# Window_Garden.net
KiCad netlist of a schematic drawn in Altium Designer
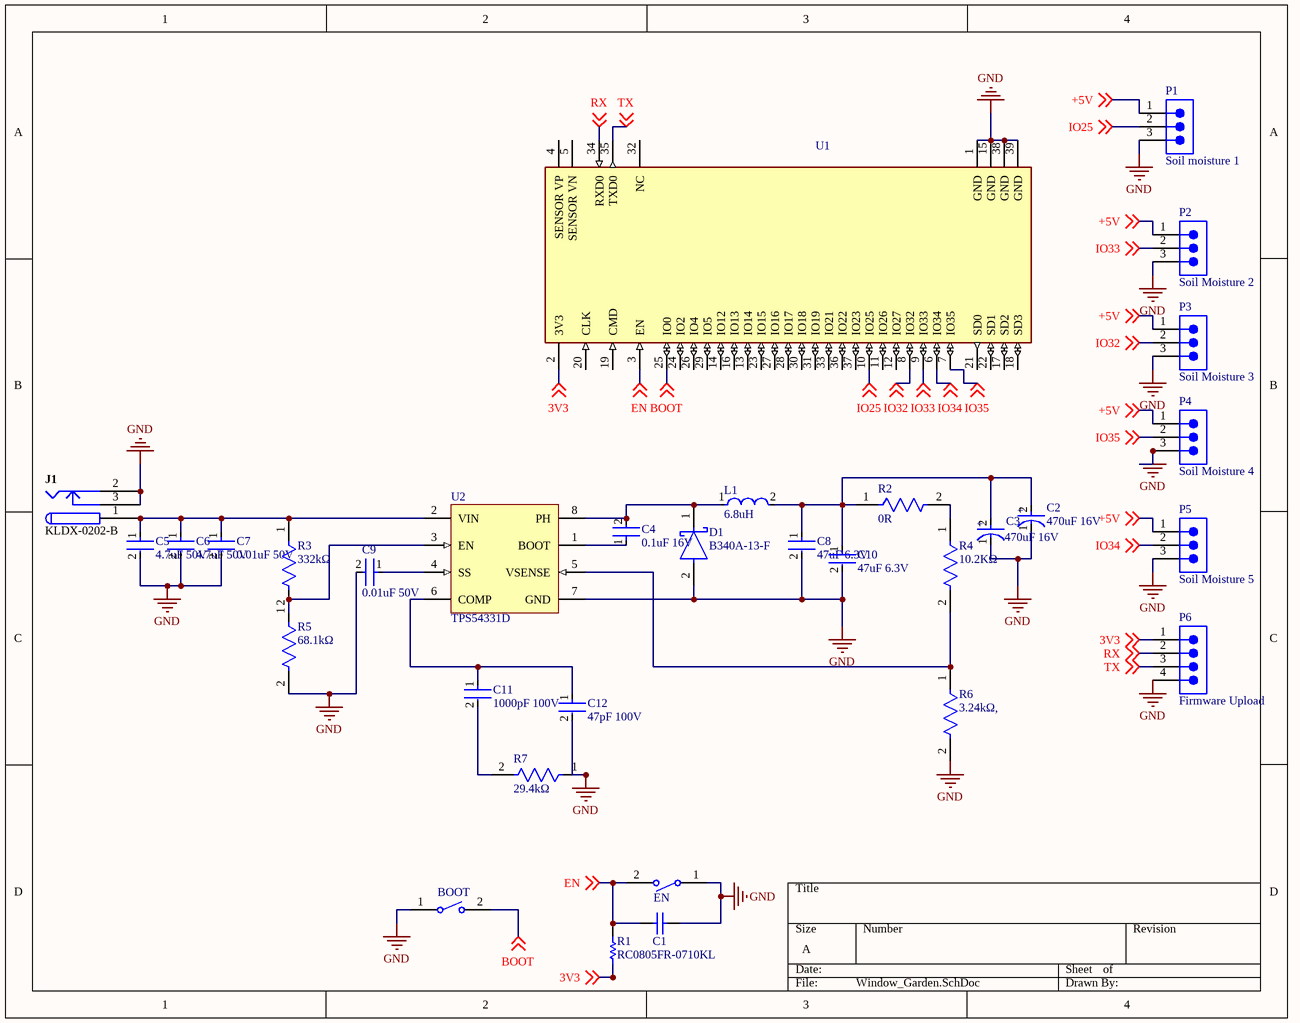
[diagram p0: Window_Garden.SchDoc]

(export (version "E")
  (design (tool "Eeschema 10.0.6"))
  (components
    (comp (ref "BOOT")
      (value "FSMSMTR")
      (footprint "TECO-FSMSMTR_V")
      (description "FSMSM Push Button Switch, 50 mA, -35 to 85 degC, 2-Pin SMD, RoHS, Tape and Reel")
      (fields (field (name "MANUFACTURER") "TE Connectivity"))
      (libsource (lib "Altium Content Vault") (part "SW-SPST-2_C"))
    )
    (comp (ref "C1")
      (value "GRM188R71H104KA93D")
      (footprint "CAPC1608X90X35ML10T15")
      (description "Chip Capacitor, 0.1 uF, +/- 10%, 50 V, -55 to 125 degC, 0603 (1608 Metric), RoHS, Tape and Reel")
      (fields (field (name "TOLERANCE") "10%") (field (name "VOLTAGE") "50V"))
      (libsource (lib "Altium Content Vault") (part "CAP-NP-2"))
    )
    (comp (ref "C2")
      (value "470uF 16V")
      (footprint "FP-RAD-TH-D_8_0_5-L_11_5-MFG")
      (description "Aluminum Electrolytic Capacitors (Radial Lead Type) 470uF ±20% 16V")
      (fields (field (name "TOLERANCE") "20%"))
      (libsource (lib "Altium Content Vault") (part "a00bbbee19879c290e62620ae7e47b1"))
    )
    (comp (ref "C3")
      (value "470uF 16V")
      (footprint "FP-RAD-TH-D_8_0_5-L_11_5-MFG")
      (description "Aluminum Electrolytic Capacitors (Radial Lead Type) 470uF ±20% 16V")
      (fields (field (name "TOLERANCE") "20%"))
      (libsource (lib "Altium Content Vault") (part "a00bbbee19879c290e62620ae7e47b1"))
    )
    (comp (ref "C4")
      (value "0.1uF 16V")
      (footprint "FP-C0805C-DN-MFG")
      (description "CAP CER 0.1UF 16V X7R 0805")
      (fields
        (field (name "OCTOPART") "https://octopart.com/c0805c104k4ractu-kemet-92155")
        (field (name "TOLERANCE") "0.1")
      )
      (libsource (lib "Altium Content Vault") (part "b4654b650e69147ec39a6b967a45e02"))
    )
    (comp (ref "C5")
      (value "4.7uF 50V")
      (footprint "FP-C1206C475K5PACTU-MFG")
      (description "CAP CER 4.7UF 50V X5R 1206")
      (fields (field (name "TOLERANCE") "10%") (field (name "VOLTAGE") "50V"))
      (libsource (lib "Altium Content Vault") (part "b4654b650e69147ec39a6b967a45e02"))
    )
    (comp (ref "C6")
      (value "4.7uF 50V")
      (footprint "FP-C1206C475K5PACTU-MFG")
      (description "CAP CER 4.7UF 50V X5R 1206")
      (fields (field (name "TOLERANCE") "10%") (field (name "VOLTAGE") "50V"))
      (libsource (lib "Altium Content Vault") (part "b4654b650e69147ec39a6b967a45e02"))
    )
    (comp (ref "C7")
      (value "0.01uF 50V")
      (footprint "FP-C1206C-EB-MFG")
      (description "CAP CER 10000PF 50V X7R 1206")
      (fields
        (field (name "OCTOPART") "https://octopart.com/c1206c103k5ractu-kemet-130245")
        (field (name "MANUFACTURER") "KEMET")
      )
      (libsource (lib "Altium Content Vault") (part "b4654b650e69147ec39a6b967a45e02"))
    )
    (comp (ref "C8")
      (value "47uF 6.3V")
      (footprint "FP-CL31-IPC_C")
      (description "Cap Ceramic 47uF 6.3V X5R ±20% SMD 1206 +85°C Embossed T/R")
      (fields (field (name "TOLERANCE") "20%") (field (name "VOLTAGE") "6.3V"))
      (libsource (lib "Altium Content Vault") (part "b4654b650e69147ec39a6b967a45e02"))
    )
    (comp (ref "C9")
      (value "0.01uF 50V")
      (footprint "FP-C1206C-EB-MFG")
      (description "CAP CER 10000PF 50V X7R 1206")
      (fields
        (field (name "OCTOPART") "https://octopart.com/c1206c103k5ractu-kemet-130245")
        (field (name "MANUFACTURER") "KEMET")
      )
      (libsource (lib "Altium Content Vault") (part "b4654b650e69147ec39a6b967a45e02"))
    )
    (comp (ref "C10")
      (value "47uF 6.3V")
      (footprint "FP-CL31-IPC_C")
      (description "Cap Ceramic 47uF 6.3V X5R ±20% SMD 1206 +85°C Embossed T/R")
      (fields (field (name "TOLERANCE") "20%") (field (name "VOLTAGE") "6.3V"))
      (libsource (lib "Altium Content Vault") (part "b4654b650e69147ec39a6b967a45e02"))
    )
    (comp (ref "C11")
      (value "1000pF 100V")
      (footprint "FP-C0805C-DN-MFG")
      (description "CAP CER 1000PF 100V X7R 0805")
      (fields (field (name "MANUFACTURER PART NUMBER") "C0805C102K1RACTU") (field (name "TOLERANCE") "0.1"))
      (libsource (lib "Altium Content Vault") (part "b4654b650e69147ec39a6b967a45e02"))
    )
    (comp (ref "C12")
      (value "47pF 100V")
      (footprint "FP-C0805C-DN-MFG")
      (description "CAP CER 47PF 100V 5% NP0 0805")
      (fields
        (field (name "MANUFACTURER") "KEMET")
        (field (name "OCTOPART") "https://octopart.com/c0805c470j1gactu-kemet-9138638")
      )
      (libsource (lib "Altium Content Vault") (part "b4654b650e69147ec39a6b967a45e02"))
    )
    (comp (ref "D1")
      (value "B340A-13-F")
      (footprint "FP-SMA-MFG")
      (description "DIODE SCHOTTKY 40V 3A SMA")
      (fields (field (name "VOLTAGE") "40V"))
      (libsource (lib "Altium Content Vault") (part "1d6ec82d83fb6aee721767c19dac4b9"))
    )
    (comp (ref "EN")
      (value "FSMSMTR")
      (footprint "TECO-FSMSMTR_V")
      (description "FSMSM Push Button Switch, 50 mA, -35 to 85 degC, 2-Pin SMD, RoHS, Tape and Reel")
      (fields (field (name "MANUFACTURER") "TE Connectivity"))
      (libsource (lib "Altium Content Vault") (part "SW-SPST-2_C"))
    )
    (comp (ref "J1")
      (value "KLDX-0202-B")
      (footprint "KYCN-KLDX-0202-B_V")
      (description "3 Conductor Power Jack, 2 break 2 aux contacts")
      (libsource (lib "Altium Content Vault") (part "KYCN-KLDX-0202-B-3"))
    )
    (comp (ref "L1")
      (value "6.8uH")
      (footprint "FP-NR8040-H_4_2-MFG")
      (description "Shielded Wirewound Inductor 6.8uH 30% 4.4A 32.5mΩ SMD")
      (fields (field (name "TOLERANCE") "30%"))
      (libsource (lib "Altium Content Vault") (part "725321dda6339637d4d059423bc1c3c"))
    )
    (comp (ref "P1")
      (value "Soil moisture 1")
      (footprint "691312510003")
      (fields (field (name "VOLTAGE") "300V"))
      (libsource (lib "Altium Content Vault") (part "TBL - 1R - 03P - Male"))
    )
    (comp (ref "P2")
      (value "Soil Moisture 2")
      (footprint "691312510003")
      (fields (field (name "VOLTAGE") "300V"))
      (libsource (lib "Altium Content Vault") (part "TBL - 1R - 03P - Male"))
    )
    (comp (ref "P3")
      (value "Soil Moisture 3")
      (footprint "691312510003")
      (fields (field (name "VOLTAGE") "300V"))
      (libsource (lib "Altium Content Vault") (part "TBL - 1R - 03P - Male"))
    )
    (comp (ref "P4")
      (value "Soil Moisture 4")
      (footprint "691312510003")
      (fields (field (name "VOLTAGE") "300V"))
      (libsource (lib "Altium Content Vault") (part "TBL - 1R - 03P - Male"))
    )
    (comp (ref "P5")
      (value "Soil Moisture 5")
      (footprint "691312510003")
      (fields (field (name "VOLTAGE") "300V"))
      (libsource (lib "Altium Content Vault") (part "TBL - 1R - 03P - Male"))
    )
    (comp (ref "P6")
      (value "Firmware Upload")
      (footprint "61300411121")
      (libsource (lib "Altium Content Vault") (part "Header_Male_1R_04P"))
    )
    (comp (ref "R1")
      (value "RC0805FR-0710KL")
      (footprint "RESC2013X60X35NL10T20")
      (description "Chip Resistor, 10 KOhm, +/- 1%, 0.125 W, -55 to 155 degC, 0805 (2012 Metric), RoHS, Tape and Reel")
      (fields (field (name "MANUFACTURER") "Yageo"))
      (libsource (lib "Altium Content Vault") (part "RES-2"))
    )
    (comp (ref "R2")
      (value "0R")
      (footprint "FP-CRCW1206-MFG")
      (description "CRCW12060000ZSTA Zero Ohm Resistor, Jumper, 1206 [3216 Metric], Thick Film, 250 mW, Surface Mount")
      (libsource (lib "Altium Content Vault") (part "1029c3af85768c4190bb7ad29bc67b5"))
    )
    (comp (ref "R3")
      (value "332kΩ")
      (footprint "FP-RMCF1206-IPC_A")
      (description "332kΩ ±1% 0.25W 1206 Thick Film Chip Resistor AEC-Q200 compliant")
      (fields (field (name "TOLERANCE") "1%"))
      (libsource (lib "Altium Content Vault") (part "1029c3af85768c4190bb7ad29bc67b5"))
    )
    (comp (ref "R4")
      (value "10.2KΩ")
      (footprint "FP-RP732B-MFG")
      (description "Res Thin Film 1206 10.2KΩ 0.1% 0.25W 15ppm/°C Molded SMD")
      (fields
        (field (name "MANUFACTURER PART NUMBER") "RP73D2B10K2BTG")
        (field (name "MANUFACTURER") "TE Connectivity")
      )
      (libsource (lib "Altium Content Vault") (part "1029c3af85768c4190bb7ad29bc67b5"))
    )
    (comp (ref "R5")
      (value "68.1kΩ")
      (footprint "FP-RNCP1206-MFG")
      (description "68.1kΩ ±1% 0.5W 1206 High Power Anti-Sulfur Thin Film Chip Resistor")
      (fields (field (name "TOLERANCE") "1%"))
      (libsource (lib "Altium Content Vault") (part "1029c3af85768c4190bb7ad29bc67b5"))
    )
    (comp (ref "R6")
      (value "3.24kΩ,")
      (footprint "FP-RG3216-IPC_A")
      (description "Automotive Metal Thin Film Chip Resistor, 1206, 3.24kΩ, 0.1%, 5ppm/°C, 0.25W, 200V")
      (fields (field (name "TOLERANCE") "0.1%"))
      (libsource (lib "Altium Content Vault") (part "1029c3af85768c4190bb7ad29bc67b5"))
    )
    (comp (ref "R7")
      (value "29.4kΩ")
      (footprint "FP-MCR18-MFG")
      (description "Thick Film Chip Resistor, 1206, 29.4kΩ, 1%, 100ppm/°C, 0.25W, 200V")
      (fields (field (name "TOLERANCE") "1%"))
      (libsource (lib "Altium Content Vault") (part "1029c3af85768c4190bb7ad29bc67b5"))
    )
    (comp (ref "U1")
      (value "ESP32-WROOM-32D (16MB)")
      (footprint "FP-ESP32-WROOM-32D_16MB-MFG")
      (description "RX TXRX MOD WIFI TRACE ANT SMD")
      (libsource (lib "Altium Content Vault") (part "0f6efa1e107731c2e5e3f960d62f5e3"))
    )
    (comp (ref "U2")
      (value "TPS54331D")
      (footprint "D0008A_L")
      (fields (field (name "MANUFACTURER") "Texas Instruments"))
      (libsource (lib "Altium Content Vault") (part "TI-TPS54331D8"))
    )
  )
  (nets
    (net (code "1") (name "+5V") (class "Default")
      (node (ref "P1") (pin "1") (pinfunction "1_1") (pintype "passive"))
      (node (ref "P2") (pin "1") (pinfunction "1_1") (pintype "passive"))
      (node (ref "P3") (pin "1") (pinfunction "1_1") (pintype "passive"))
      (node (ref "P4") (pin "1") (pinfunction "1_1") (pintype "passive"))
      (node (ref "P5") (pin "1") (pinfunction "1_1") (pintype "passive"))
    )
    (net (code "2") (name "3V3") (class "Default")
      (node (ref "P6") (pin "1") (pinfunction "1_1") (pintype "passive"))
      (node (ref "R1") (pin "1") (pinfunction "1_1") (pintype "passive"))
      (node (ref "U1") (pin "2") (pinfunction "3V3_2") (pintype "power_in"))
    )
    (net (code "3") (name "BOOT") (class "Default")
      (node (ref "BOOT") (pin "2") (pinfunction "2_2") (pintype "passive"))
      (node (ref "U1") (pin "25") (pinfunction "IO0_25") (pintype "bidirectional"))
    )
    (net (code "4") (name "EN") (class "Default")
      (node (ref "C1") (pin "2") (pinfunction "2_2") (pintype "passive"))
      (node (ref "EN") (pin "2") (pinfunction "2_2") (pintype "passive"))
      (node (ref "R1") (pin "2") (pinfunction "2_2") (pintype "passive"))
      (node (ref "U1") (pin "3") (pinfunction "EN_3") (pintype "input"))
    )
    (net (code "5") (name "GND") (class "Default")
      (node (ref "BOOT") (pin "1") (pinfunction "1_1") (pintype "passive"))
      (node (ref "C1") (pin "1") (pinfunction "1_1") (pintype "passive"))
      (node (ref "C10") (pin "2") (pinfunction "2_2") (pintype "passive"))
      (node (ref "C12") (pin "2") (pinfunction "2_2") (pintype "passive"))
      (node (ref "C2") (pin "1") (pinfunction "C_1") (pintype "passive"))
      (node (ref "C3") (pin "1") (pinfunction "C_1") (pintype "passive"))
      (node (ref "C5") (pin "2") (pinfunction "2_2") (pintype "passive"))
      (node (ref "C6") (pin "2") (pinfunction "2_2") (pintype "passive"))
      (node (ref "C7") (pin "2") (pinfunction "2_2") (pintype "passive"))
      (node (ref "C8") (pin "2") (pinfunction "2_2") (pintype "passive"))
      (node (ref "C9") (pin "2") (pinfunction "2_2") (pintype "passive"))
      (node (ref "D1") (pin "2") (pinfunction "A_2") (pintype "passive"))
      (node (ref "EN") (pin "1") (pinfunction "1_1") (pintype "passive"))
      (node (ref "J1") (pin "2") (pintype "power_in"))
      (node (ref "J1") (pin "3") (pintype "power_in"))
      (node (ref "P1") (pin "3") (pinfunction "3_3") (pintype "passive"))
      (node (ref "P2") (pin "3") (pinfunction "3_3") (pintype "passive"))
      (node (ref "P3") (pin "3") (pinfunction "3_3") (pintype "passive"))
      (node (ref "P4") (pin "3") (pinfunction "3_3") (pintype "passive"))
      (node (ref "P5") (pin "3") (pinfunction "3_3") (pintype "passive"))
      (node (ref "P6") (pin "4") (pinfunction "4_4") (pintype "passive"))
      (node (ref "R5") (pin "2") (pinfunction "2_2") (pintype "passive"))
      (node (ref "R6") (pin "2") (pinfunction "2_2") (pintype "passive"))
      (node (ref "R7") (pin "1") (pinfunction "1_1") (pintype "passive"))
      (node (ref "U1") (pin "1") (pinfunction "GND_1") (pintype "power_in"))
      (node (ref "U1") (pin "15") (pinfunction "GND_15") (pintype "power_in"))
      (node (ref "U1") (pin "38") (pinfunction "GND_38") (pintype "power_in"))
      (node (ref "U1") (pin "39") (pinfunction "GND_39") (pintype "power_in"))
      (node (ref "U2") (pin "7") (pinfunction "GND_7") (pintype "power_in"))
    )
    (net (code "6") (name "IO25") (class "Default")
      (node (ref "P1") (pin "2") (pinfunction "2_2") (pintype "passive"))
      (node (ref "U1") (pin "10") (pinfunction "IO25_10") (pintype "bidirectional"))
    )
    (net (code "7") (name "IO32") (class "Default")
      (node (ref "P3") (pin "2") (pinfunction "2_2") (pintype "passive"))
      (node (ref "U1") (pin "8") (pinfunction "IO32_8") (pintype "bidirectional"))
    )
    (net (code "8") (name "IO33") (class "Default")
      (node (ref "P2") (pin "2") (pinfunction "2_2") (pintype "passive"))
      (node (ref "U1") (pin "9") (pinfunction "IO33_9") (pintype "bidirectional"))
    )
    (net (code "9") (name "IO34") (class "Default")
      (node (ref "P5") (pin "2") (pinfunction "2_2") (pintype "passive"))
      (node (ref "U1") (pin "6") (pinfunction "IO34_6") (pintype "bidirectional"))
    )
    (net (code "10") (name "IO35") (class "Default")
      (node (ref "P4") (pin "2") (pinfunction "2_2") (pintype "passive"))
      (node (ref "U1") (pin "7") (pinfunction "IO35_7") (pintype "bidirectional"))
    )
    (net (code "11") (name "Net-(C2-A)") (class "Default")
      (node (ref "C10") (pin "1") (pinfunction "1_1") (pintype "passive"))
      (node (ref "C2") (pin "2") (pinfunction "A_2") (pintype "passive"))
      (node (ref "C3") (pin "2") (pinfunction "A_2") (pintype "passive"))
      (node (ref "C8") (pin "1") (pinfunction "1_1") (pintype "passive"))
      (node (ref "L1") (pin "2") (pinfunction "2_2") (pintype "passive"))
      (node (ref "R2") (pin "1") (pinfunction "1_1") (pintype "passive"))
    )
    (net (code "12") (name "Net-(C11-Pad2)") (class "Default")
      (node (ref "C11") (pin "2") (pinfunction "2_2") (pintype "passive"))
      (node (ref "R7") (pin "2") (pinfunction "2_2") (pintype "passive"))
    )
    (net (code "13") (name "Net-(D1-C)") (class "Default")
      (node (ref "C4") (pin "2") (pinfunction "2_2") (pintype "passive"))
      (node (ref "D1") (pin "1") (pinfunction "C_1") (pintype "passive"))
      (node (ref "L1") (pin "1") (pinfunction "1_1") (pintype "passive"))
      (node (ref "U2") (pin "8") (pinfunction "PH_8") (pintype "power_in"))
    )
    (net (code "14") (name "Net-(R2-Pad2)") (class "Default")
      (node (ref "R2") (pin "2") (pinfunction "2_2") (pintype "passive"))
      (node (ref "R4") (pin "1") (pinfunction "1_1") (pintype "passive"))
    )
    (net (code "15") (name "Net-(U2-BOOT)") (class "Default")
      (node (ref "C4") (pin "1") (pinfunction "1_1") (pintype "passive"))
      (node (ref "U2") (pin "1") (pinfunction "BOOT_1") (pintype "passive"))
    )
    (net (code "16") (name "Net-(U2-COMP)") (class "Default")
      (node (ref "C11") (pin "1") (pinfunction "1_1") (pintype "passive"))
      (node (ref "C12") (pin "1") (pinfunction "1_1") (pintype "passive"))
      (node (ref "U2") (pin "6") (pinfunction "COMP_6") (pintype "passive"))
    )
    (net (code "17") (name "Net-(U2-EN)") (class "Default")
      (node (ref "R3") (pin "2") (pinfunction "2_2") (pintype "passive"))
      (node (ref "R5") (pin "1") (pinfunction "1_1") (pintype "passive"))
      (node (ref "U2") (pin "3") (pinfunction "EN_3") (pintype "input"))
    )
    (net (code "18") (name "Net-(U2-SS)") (class "Default")
      (node (ref "C9") (pin "1") (pinfunction "1_1") (pintype "passive"))
      (node (ref "U2") (pin "4") (pinfunction "SS_4") (pintype "input"))
    )
    (net (code "19") (name "Net-(U2-VIN)") (class "Default")
      (node (ref "C5") (pin "1") (pinfunction "1_1") (pintype "passive"))
      (node (ref "C6") (pin "1") (pinfunction "1_1") (pintype "passive"))
      (node (ref "C7") (pin "1") (pinfunction "1_1") (pintype "passive"))
      (node (ref "J1") (pin "1") (pintype "power_in"))
      (node (ref "R3") (pin "1") (pinfunction "1_1") (pintype "passive"))
      (node (ref "U2") (pin "2") (pinfunction "VIN_2") (pintype "power_in"))
    )
    (net (code "20") (name "Net-(U2-VSENSE)") (class "Default")
      (node (ref "R4") (pin "2") (pinfunction "2_2") (pintype "passive"))
      (node (ref "R6") (pin "1") (pinfunction "1_1") (pintype "passive"))
      (node (ref "U2") (pin "5") (pinfunction "VSENSE_5") (pintype "input"))
    )
    (net (code "21") (name "RX") (class "Default")
      (node (ref "P6") (pin "2") (pinfunction "2_2") (pintype "passive"))
      (node (ref "U1") (pin "34") (pinfunction "RXD0_34") (pintype "input"))
    )
    (net (code "22") (name "TX") (class "Default")
      (node (ref "P6") (pin "3") (pinfunction "3_3") (pintype "passive"))
      (node (ref "U1") (pin "35") (pinfunction "TXD0_35") (pintype "output"))
    )
    (net (code "23") (name "unconnected-(U1-CLK-Pad20)") (class "Default")
      (node (ref "U1") (pin "20") (pinfunction "CLK_20") (pintype "input"))
    )
    (net (code "24") (name "unconnected-(U1-CMD-Pad19)") (class "Default")
      (node (ref "U1") (pin "19") (pinfunction "CMD_19") (pintype "input"))
    )
    (net (code "25") (name "unconnected-(U1-IO2-Pad24)") (class "Default")
      (node (ref "U1") (pin "24") (pinfunction "IO2_24") (pintype "bidirectional"))
    )
    (net (code "26") (name "unconnected-(U1-IO4-Pad26)") (class "Default")
      (node (ref "U1") (pin "26") (pinfunction "IO4_26") (pintype "bidirectional"))
    )
    (net (code "27") (name "unconnected-(U1-IO5-Pad29)") (class "Default")
      (node (ref "U1") (pin "29") (pinfunction "IO5_29") (pintype "bidirectional"))
    )
    (net (code "28") (name "unconnected-(U1-IO12-Pad14)") (class "Default")
      (node (ref "U1") (pin "14") (pinfunction "IO12_14") (pintype "bidirectional"))
    )
    (net (code "29") (name "unconnected-(U1-IO13-Pad16)") (class "Default")
      (node (ref "U1") (pin "16") (pinfunction "IO13_16") (pintype "bidirectional"))
    )
    (net (code "30") (name "unconnected-(U1-IO14-Pad13)") (class "Default")
      (node (ref "U1") (pin "13") (pinfunction "IO14_13") (pintype "bidirectional"))
    )
    (net (code "31") (name "unconnected-(U1-IO15-Pad23)") (class "Default")
      (node (ref "U1") (pin "23") (pinfunction "IO15_23") (pintype "bidirectional"))
    )
    (net (code "32") (name "unconnected-(U1-IO16-Pad27)") (class "Default")
      (node (ref "U1") (pin "27") (pinfunction "IO16_27") (pintype "bidirectional"))
    )
    (net (code "33") (name "unconnected-(U1-IO17-Pad28)") (class "Default")
      (node (ref "U1") (pin "28") (pinfunction "IO17_28") (pintype "bidirectional"))
    )
    (net (code "34") (name "unconnected-(U1-IO18-Pad30)") (class "Default")
      (node (ref "U1") (pin "30") (pinfunction "IO18_30") (pintype "bidirectional"))
    )
    (net (code "35") (name "unconnected-(U1-IO19-Pad31)") (class "Default")
      (node (ref "U1") (pin "31") (pinfunction "IO19_31") (pintype "bidirectional"))
    )
    (net (code "36") (name "unconnected-(U1-IO21-Pad33)") (class "Default")
      (node (ref "U1") (pin "33") (pinfunction "IO21_33") (pintype "bidirectional"))
    )
    (net (code "37") (name "unconnected-(U1-IO22-Pad36)") (class "Default")
      (node (ref "U1") (pin "36") (pinfunction "IO22_36") (pintype "bidirectional"))
    )
    (net (code "38") (name "unconnected-(U1-IO23-Pad37)") (class "Default")
      (node (ref "U1") (pin "37") (pinfunction "IO23_37") (pintype "bidirectional"))
    )
    (net (code "39") (name "unconnected-(U1-IO26-Pad11)") (class "Default")
      (node (ref "U1") (pin "11") (pinfunction "IO26_11") (pintype "bidirectional"))
    )
    (net (code "40") (name "unconnected-(U1-IO27-Pad12)") (class "Default")
      (node (ref "U1") (pin "12") (pinfunction "IO27_12") (pintype "bidirectional"))
    )
    (net (code "41") (name "unconnected-(U1-NC-Pad32)") (class "Default")
      (node (ref "U1") (pin "32") (pinfunction "NC_32") (pintype "passive"))
    )
    (net (code "42") (name "unconnected-(U1-SD0-Pad21)") (class "Default")
      (node (ref "U1") (pin "21") (pinfunction "SD0_21") (pintype "output"))
    )
    (net (code "43") (name "unconnected-(U1-SD1-Pad22)") (class "Default")
      (node (ref "U1") (pin "22") (pinfunction "SD1_22") (pintype "bidirectional"))
    )
    (net (code "44") (name "unconnected-(U1-SD2-Pad17)") (class "Default")
      (node (ref "U1") (pin "17") (pinfunction "SD2_17") (pintype "bidirectional"))
    )
    (net (code "45") (name "unconnected-(U1-SD3-Pad18)") (class "Default")
      (node (ref "U1") (pin "18") (pinfunction "SD3_18") (pintype "bidirectional"))
    )
    (net (code "46") (name "unconnected-(U1-SENSOR_VN-Pad5)") (class "Default")
      (node (ref "U1") (pin "5") (pinfunction "SENSOR_VN_5") (pintype "passive"))
    )
    (net (code "47") (name "unconnected-(U1-SENSOR_VP-Pad4)") (class "Default")
      (node (ref "U1") (pin "4") (pinfunction "SENSOR_VP_4") (pintype "passive"))
    )
  )
)
